# headstage-64-coax-adapter_rev1_1.net
KiCad netlist of a schematic drawn in EAGLE
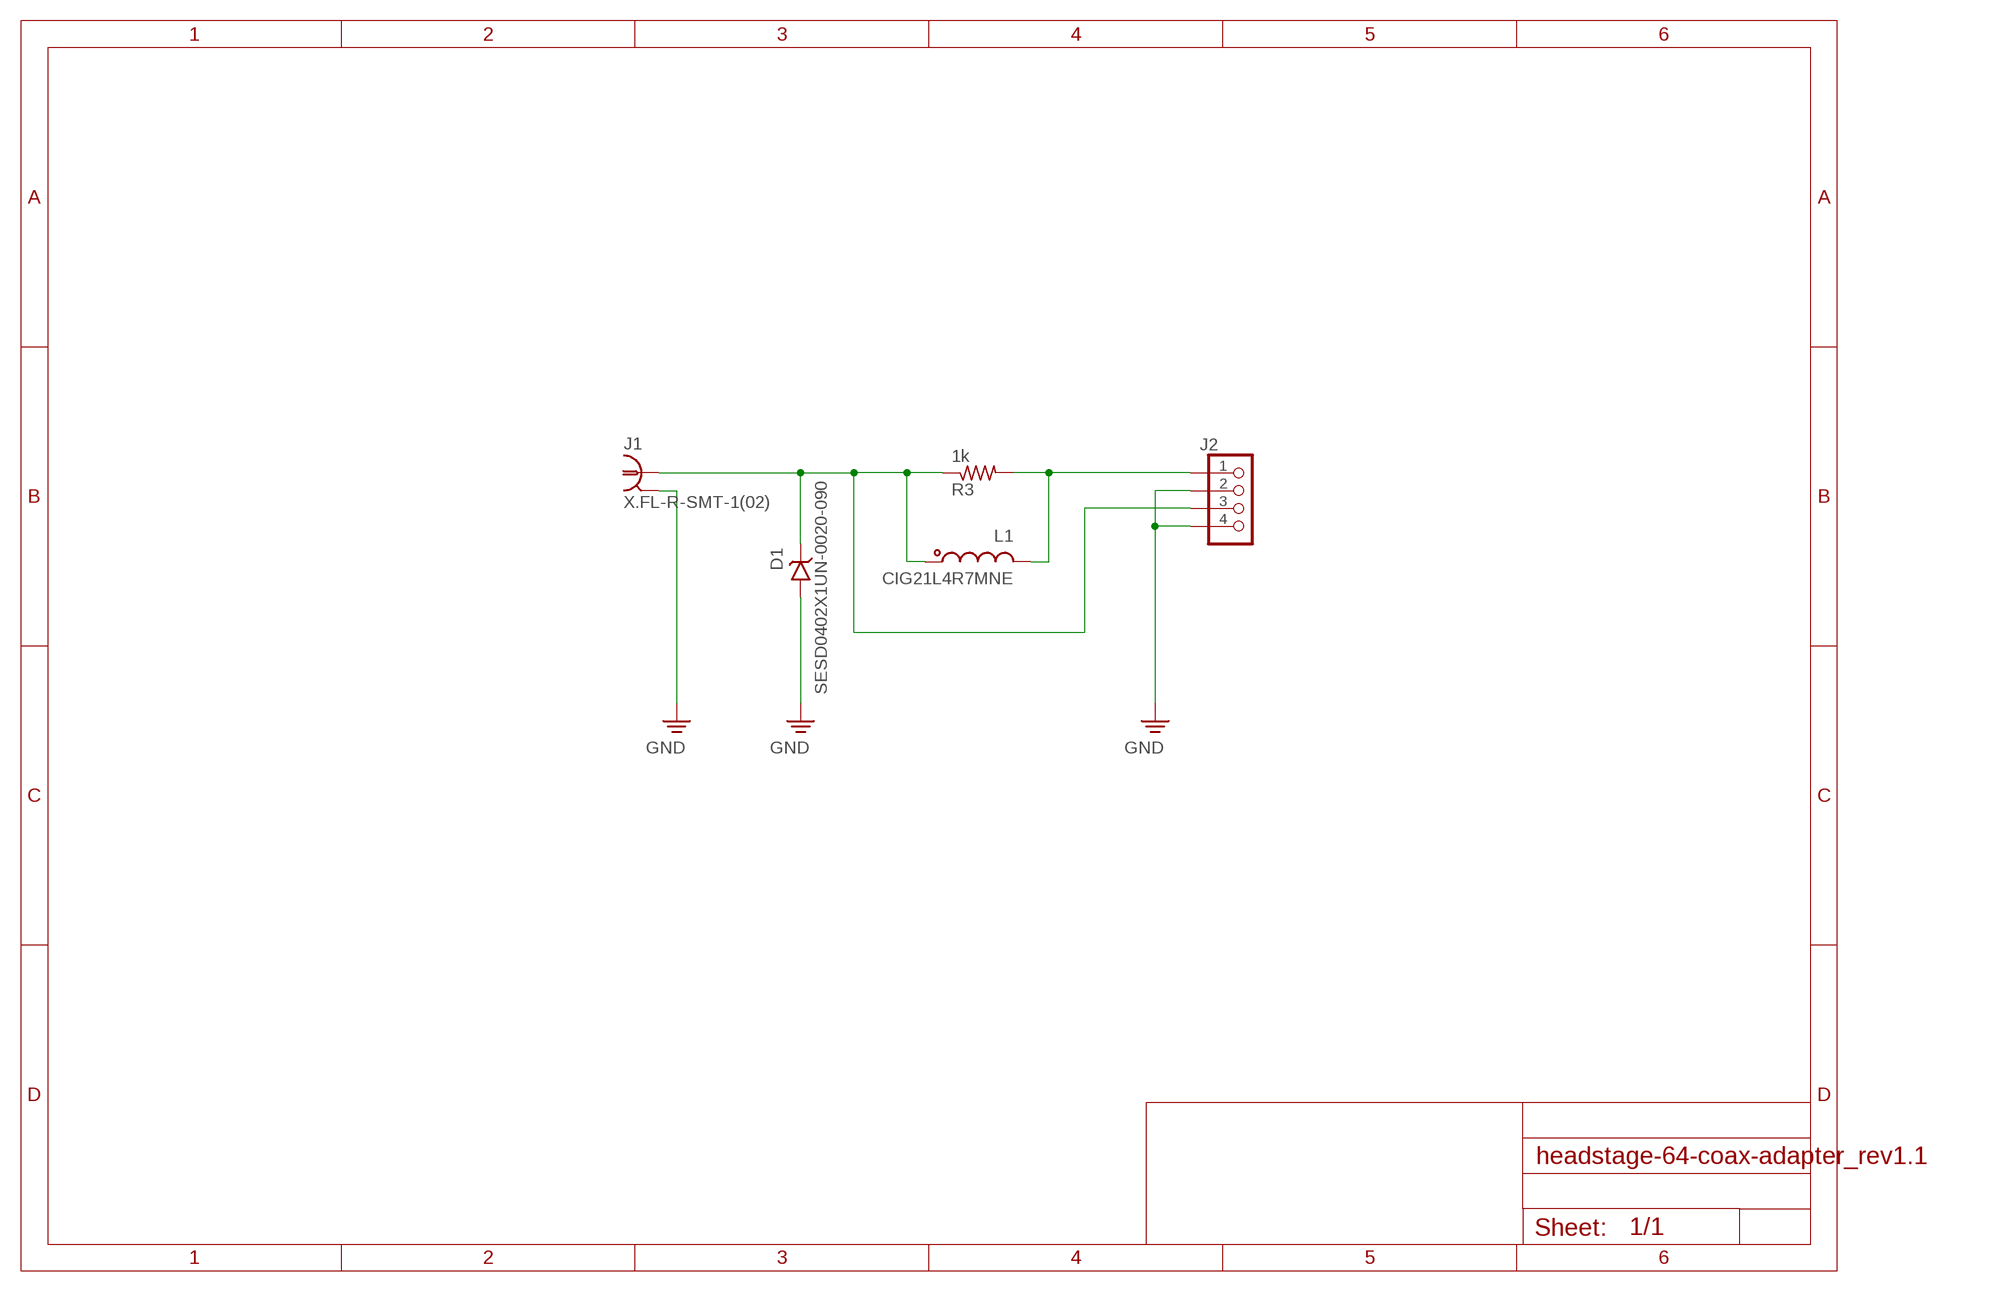
[diagram p0: schematic, sheet 1]

(export (version "E")
  (design (tool "Eeschema 10.0.6"))
  (components
    (comp (ref "D1")
      (value "SESD0402X1UN-0020-090")
      (footprint "eagle-import:0402T-DFN")
      (libsource (lib "eagle-import") (part "Z-DIODE_0402T-DFN"))
    )
    (comp (ref "J1")
      (value "X.FL-R-SMT-1(02)")
      (footprint "eagle-import:X_FL_R_SMT_1(02)")
      (libsource (lib "eagle-import") (part "COAX_XFL"))
    )
    (comp (ref "J2")
      (value "PINHD-1X4HEADSTAGE64-DAUGHTER-CARD-CASTELLATED")
      (footprint "eagle-import:HEADSTAGE64-DAUGHER-CARD-CASTELLATED")
      (libsource (lib "eagle-import") (part "PINHD-1X4HEADSTAGE64-DAUGHTER-CARD-CASTELLATED"))
    )
    (comp (ref "L1")
      (value "CIG21L4R7MNE")
      (footprint "eagle-import:0805T")
      (libsource (lib "eagle-import") (part "L_0805T"))
    )
    (comp (ref "R3")
      (value "1k")
      (footprint "eagle-import:0201T")
      (libsource (lib "eagle-import") (part "R_0201T"))
    )
  )
  (nets
    (net (code "1") (name "GND") (class "Default")
      (node (ref "D1") (pin "A") (pinfunction "A_A") (pintype "passive"))
      (node (ref "J1") (pin "P$2") (pinfunction "2_P$2") (pintype "passive"))
      (node (ref "J1") (pin "P$3") (pinfunction "2_P$3") (pintype "passive"))
      (node (ref "J1") (pin "P$4") (pinfunction "2_P$4") (pintype "passive"))
      (node (ref "J2") (pin "2") (pinfunction "2_2") (pintype "passive"))
      (node (ref "J2") (pin "4") (pinfunction "4_4") (pintype "passive"))
    )
    (net (code "2") (name "Net-(J1-1)") (class "Default")
      (node (ref "D1") (pin "C") (pinfunction "C_C") (pintype "passive"))
      (node (ref "J1") (pin "P$1") (pinfunction "1_P$1") (pintype "passive"))
      (node (ref "J2") (pin "3") (pinfunction "3_3") (pintype "passive"))
      (node (ref "L1") (pin "1") (pinfunction "1_1") (pintype "passive"))
      (node (ref "R3") (pin "1") (pinfunction "1_1") (pintype "passive"))
    )
    (net (code "3") (name "Net-(J2-Pad1)") (class "Default")
      (node (ref "J2") (pin "1") (pinfunction "1_1") (pintype "passive"))
      (node (ref "L1") (pin "2") (pinfunction "2_2") (pintype "passive"))
      (node (ref "R3") (pin "2") (pinfunction "2_2") (pintype "passive"))
    )
  )
)
